# SCH_Task_10_1.net
KiCad netlist of a schematic drawn in EasyEDA
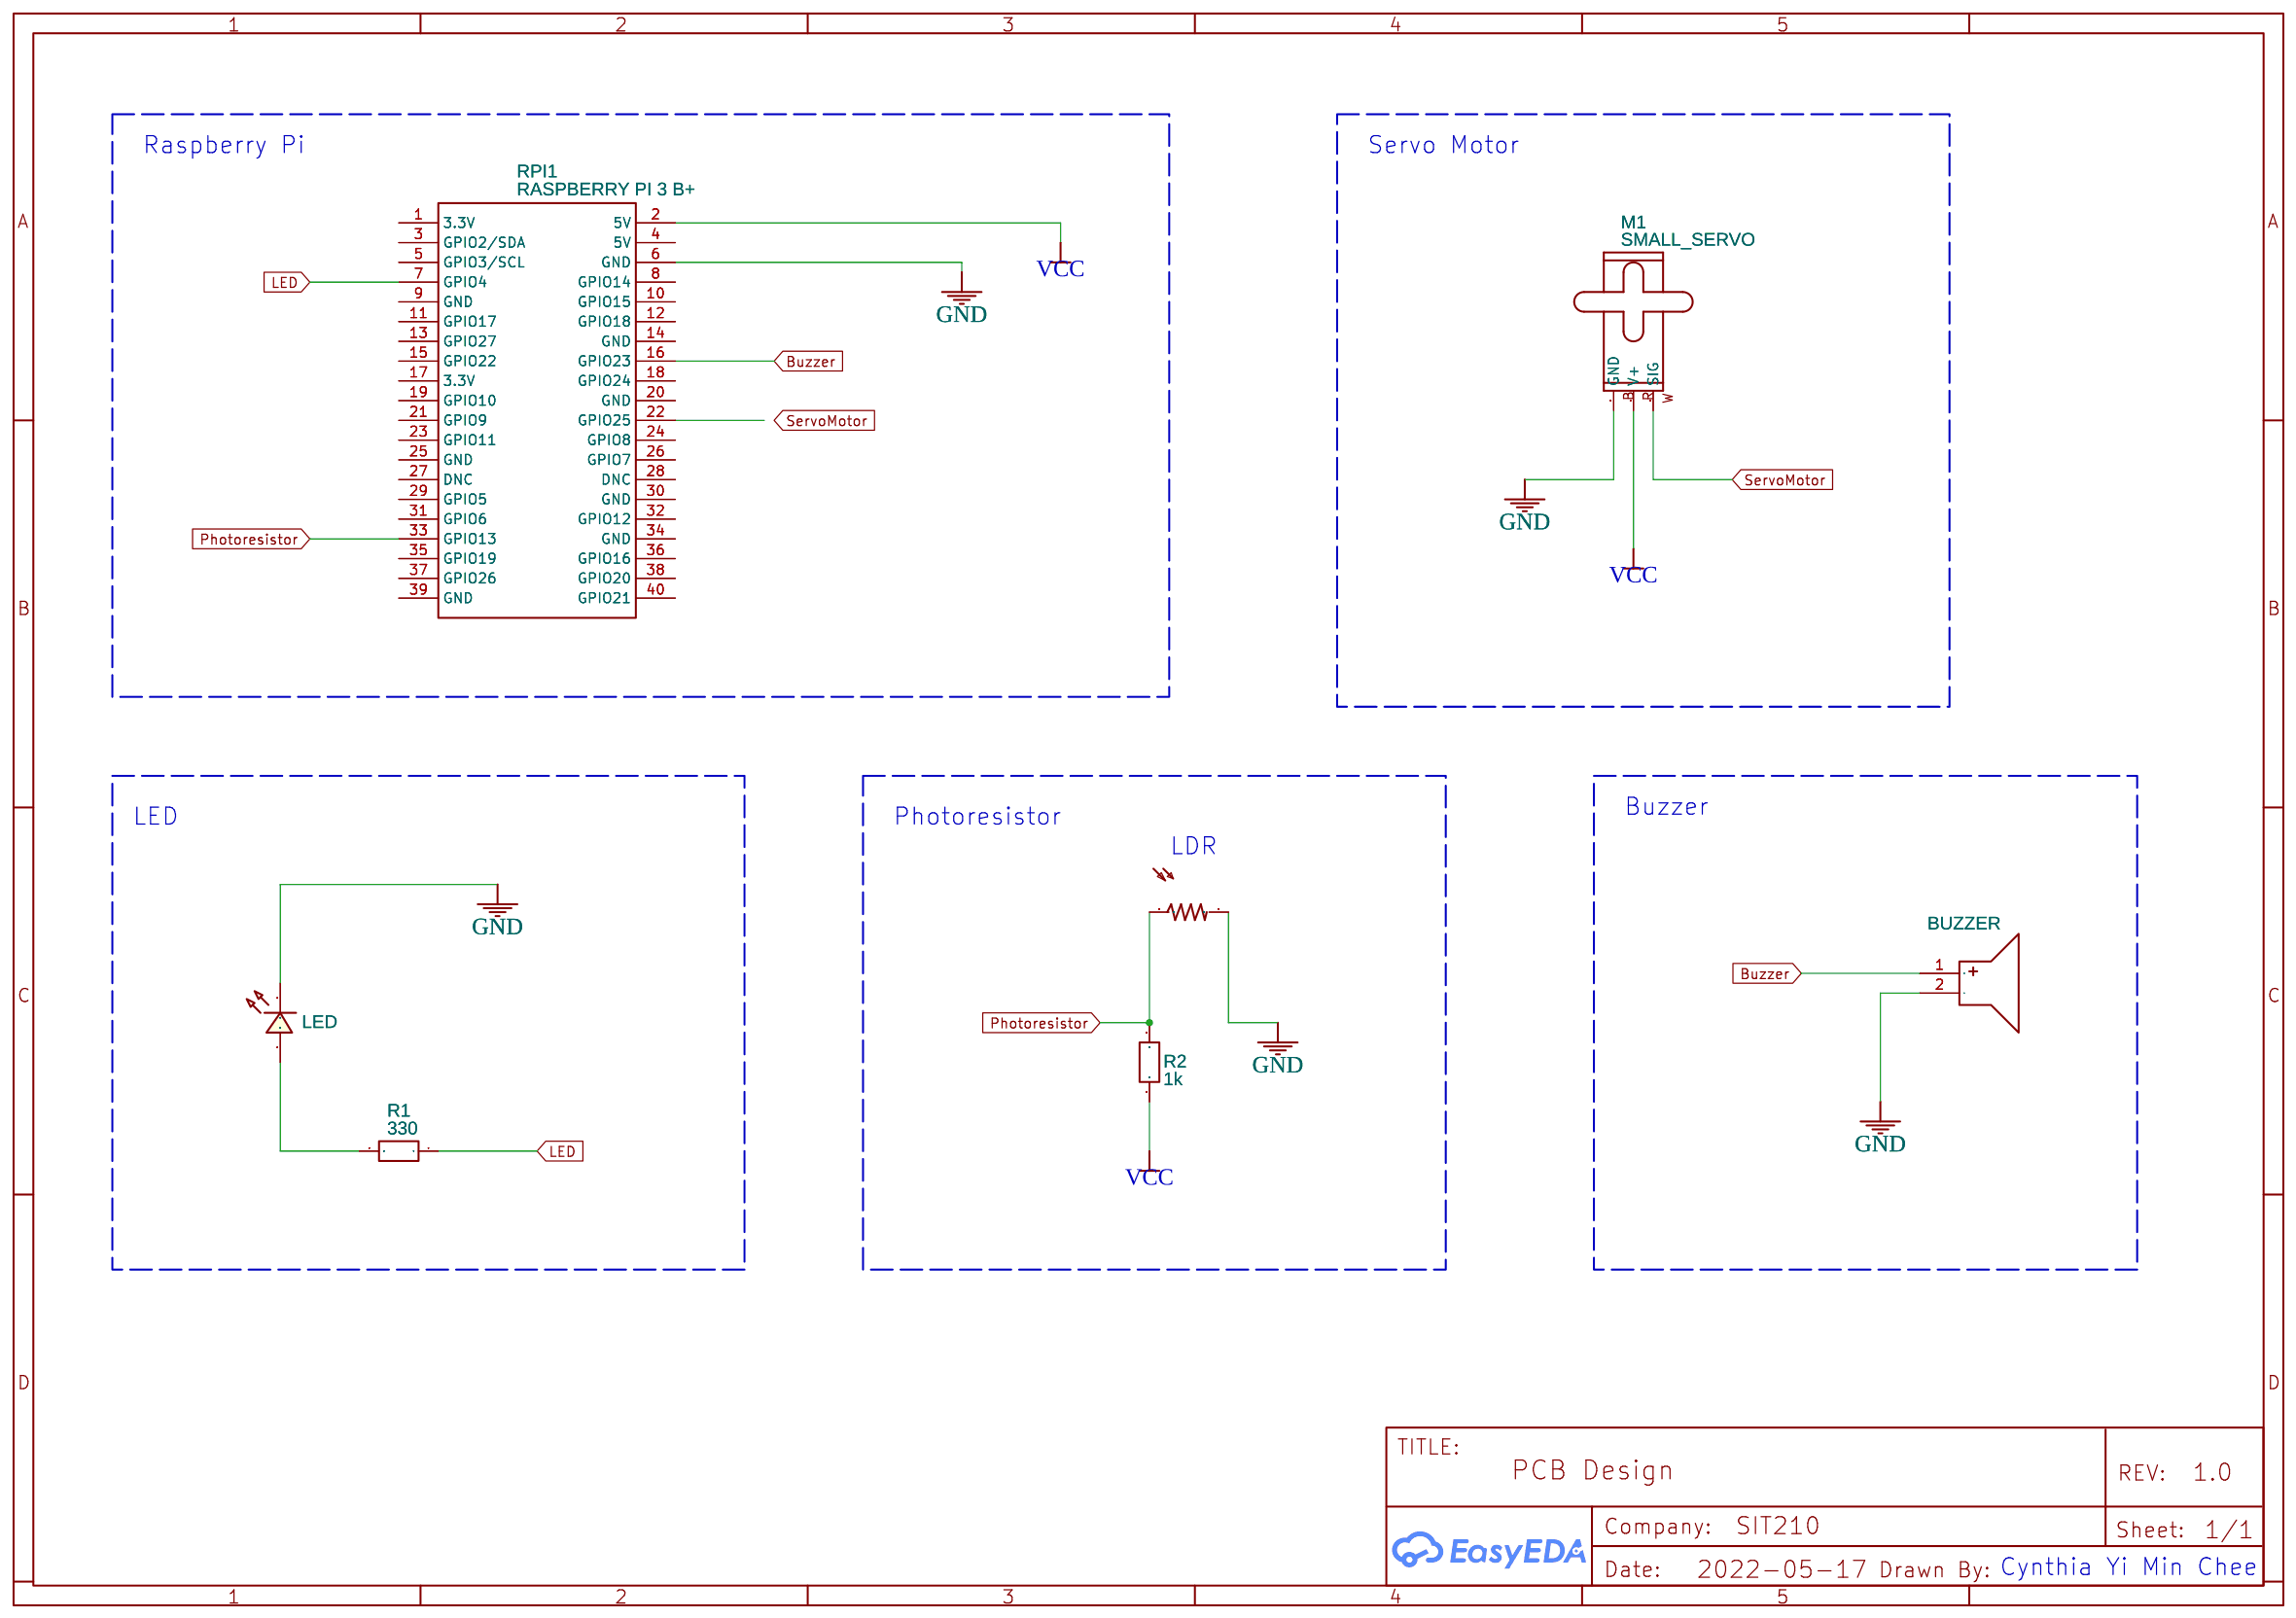
[diagram p0: schematic sheet]

(export (version "E")
  (design (tool "Eeschema 10.0.6"))
  (components
    (comp (ref "BUZZER")
      (value "BUZZER.9032")
      (fields (field (name "BOM_Supplier Part") "C9900002564"))
      (libsource (lib "") (part "BUZZER.9032"))
    )
    (comp (ref "LDR1") (value "LDR") (libsource (lib "") (part "LDR1")))
    (comp (ref "LED")
      (value "LED-0603_R")
      (fields
        (field (name "BOM_Manufacturer Part") "19-217/R6C-AL1M2VY/3T")
        (field (name "BOM_Supplier Part") "C72044")
      )
      (libsource (lib "") (part "LED-0603_R"))
    )
    (comp (ref "M1") (value "SMALL_SERVO") (libsource (lib "") (part "SMALL_SERVO")))
    (comp (ref "R1") (value "330") (libsource (lib "") (part "R_0603_EU")))
    (comp (ref "R2") (value "1k") (libsource (lib "") (part "R_0603_EU_1")))
    (comp (ref "RPI1")
      (value "RASPBERRY PI 3 B+")
      (fields
        (field (name "Manufacturer") "Raspberry Pi")
        (field (name "BOM_Manufacturer Part") "Raspberry Pi 3 - Model B+ - 1.4GHz Cortex-A53 with 1GB RAM")
        (field (name "BOM_Supplier Part") "3775")
      )
      (libsource (lib "") (part "RASPBERRY PI 3 B+"))
    )
  )
  (nets
    (net (code "1") (name "Buzzer") (class "Default")
      (node (ref "BUZZER") (pin "1") (pinfunction "+_1") (pintype "unspecified"))
      (node (ref "RPI1") (pin "16") (pinfunction "GPIO23_16") (pintype "bidirectional"))
    )
    (net (code "2") (name "GND") (class "Default")
      (node (ref "BUZZER") (pin "2") (pinfunction "-_2") (pintype "unspecified"))
      (node (ref "LDR1") (pin "2") (pinfunction "2_2") (pintype "bidirectional"))
      (node (ref "LED") (pin "2") (pinfunction "2_2") (pintype "unspecified"))
      (node (ref "M1") (pin "3") (pinfunction "GND_3") (pintype "unspecified"))
      (node (ref "RPI1") (pin "6") (pinfunction "GND_6") (pintype "unspecified"))
    )
    (net (code "3") (name "LED") (class "Default")
      (node (ref "R1") (pin "1") (pinfunction "1_1") (pintype "unspecified"))
      (node (ref "RPI1") (pin "7") (pinfunction "GPIO4_7") (pintype "bidirectional"))
    )
    (net (code "4") (name "Net-(LED-Pad1)") (class "Default")
      (node (ref "LED") (pin "1") (pinfunction "1_1") (pintype "unspecified"))
      (node (ref "R1") (pin "2") (pinfunction "2_2") (pintype "unspecified"))
    )
    (net (code "5") (name "Photoresistor") (class "Default")
      (node (ref "LDR1") (pin "1") (pinfunction "1_1") (pintype "bidirectional"))
      (node (ref "R2") (pin "2") (pinfunction "2_2") (pintype "unspecified"))
      (node (ref "RPI1") (pin "33") (pinfunction "GPIO13_33") (pintype "bidirectional"))
    )
    (net (code "6") (name "ServoMotor") (class "Default")
      (node (ref "M1") (pin "1") (pinfunction "SIG_1") (pintype "unspecified"))
    )
    (net (code "7") (name "VCC") (class "Default")
      (node (ref "M1") (pin "2") (pinfunction "V+_2") (pintype "unspecified"))
      (node (ref "R2") (pin "1") (pinfunction "1_1") (pintype "unspecified"))
      (node (ref "RPI1") (pin "2") (pinfunction "5V_2") (pintype "passive"))
    )
    (net (code "8") (name "unconnected-(RPI1-3.3V-Pad1)") (class "Default")
      (node (ref "RPI1") (pin "1") (pinfunction "3.3V_1") (pintype "passive"))
    )
    (net (code "9") (name "unconnected-(RPI1-3.3V-Pad17)") (class "Default")
      (node (ref "RPI1") (pin "17") (pinfunction "3.3V_17") (pintype "passive"))
    )
    (net (code "10") (name "unconnected-(RPI1-5V-Pad4)") (class "Default")
      (node (ref "RPI1") (pin "4") (pinfunction "5V_4") (pintype "passive"))
    )
    (net (code "11") (name "unconnected-(RPI1-DNC-Pad27)") (class "Default")
      (node (ref "RPI1") (pin "27") (pinfunction "DNC_27") (pintype "unspecified"))
    )
    (net (code "12") (name "unconnected-(RPI1-DNC-Pad28)") (class "Default")
      (node (ref "RPI1") (pin "28") (pinfunction "DNC_28") (pintype "unspecified"))
    )
    (net (code "13") (name "unconnected-(RPI1-GND-Pad9)") (class "Default")
      (node (ref "RPI1") (pin "9") (pinfunction "GND_9") (pintype "unspecified"))
    )
    (net (code "14") (name "unconnected-(RPI1-GND-Pad14)") (class "Default")
      (node (ref "RPI1") (pin "14") (pinfunction "GND_14") (pintype "unspecified"))
    )
    (net (code "15") (name "unconnected-(RPI1-GND-Pad20)") (class "Default")
      (node (ref "RPI1") (pin "20") (pinfunction "GND_20") (pintype "unspecified"))
    )
    (net (code "16") (name "unconnected-(RPI1-GND-Pad25)") (class "Default")
      (node (ref "RPI1") (pin "25") (pinfunction "GND_25") (pintype "unspecified"))
    )
    (net (code "17") (name "unconnected-(RPI1-GND-Pad30)") (class "Default")
      (node (ref "RPI1") (pin "30") (pinfunction "GND_30") (pintype "unspecified"))
    )
    (net (code "18") (name "unconnected-(RPI1-GND-Pad34)") (class "Default")
      (node (ref "RPI1") (pin "34") (pinfunction "GND_34") (pintype "unspecified"))
    )
    (net (code "19") (name "unconnected-(RPI1-GND-Pad39)") (class "Default")
      (node (ref "RPI1") (pin "39") (pinfunction "GND_39") (pintype "unspecified"))
    )
    (net (code "20") (name "unconnected-(RPI1-GPIO2{slash}SDA-Pad3)") (class "Default")
      (node (ref "RPI1") (pin "3") (pinfunction "GPIO2/SDA_3") (pintype "bidirectional"))
    )
    (net (code "21") (name "unconnected-(RPI1-GPIO3{slash}SCL-Pad5)") (class "Default")
      (node (ref "RPI1") (pin "5") (pinfunction "GPIO3/SCL_5") (pintype "bidirectional"))
    )
    (net (code "22") (name "unconnected-(RPI1-GPIO5-Pad29)") (class "Default")
      (node (ref "RPI1") (pin "29") (pinfunction "GPIO5_29") (pintype "bidirectional"))
    )
    (net (code "23") (name "unconnected-(RPI1-GPIO6-Pad31)") (class "Default")
      (node (ref "RPI1") (pin "31") (pinfunction "GPIO6_31") (pintype "bidirectional"))
    )
    (net (code "24") (name "unconnected-(RPI1-GPIO7-Pad26)") (class "Default")
      (node (ref "RPI1") (pin "26") (pinfunction "GPIO7_26") (pintype "bidirectional"))
    )
    (net (code "25") (name "unconnected-(RPI1-GPIO8-Pad24)") (class "Default")
      (node (ref "RPI1") (pin "24") (pinfunction "GPIO8_24") (pintype "bidirectional"))
    )
    (net (code "26") (name "unconnected-(RPI1-GPIO9-Pad21)") (class "Default")
      (node (ref "RPI1") (pin "21") (pinfunction "GPIO9_21") (pintype "bidirectional"))
    )
    (net (code "27") (name "unconnected-(RPI1-GPIO10-Pad19)") (class "Default")
      (node (ref "RPI1") (pin "19") (pinfunction "GPIO10_19") (pintype "bidirectional"))
    )
    (net (code "28") (name "unconnected-(RPI1-GPIO11-Pad23)") (class "Default")
      (node (ref "RPI1") (pin "23") (pinfunction "GPIO11_23") (pintype "bidirectional"))
    )
    (net (code "29") (name "unconnected-(RPI1-GPIO12-Pad32)") (class "Default")
      (node (ref "RPI1") (pin "32") (pinfunction "GPIO12_32") (pintype "bidirectional"))
    )
    (net (code "30") (name "unconnected-(RPI1-GPIO14-Pad8)") (class "Default")
      (node (ref "RPI1") (pin "8") (pinfunction "GPIO14_8") (pintype "bidirectional"))
    )
    (net (code "31") (name "unconnected-(RPI1-GPIO15-Pad10)") (class "Default")
      (node (ref "RPI1") (pin "10") (pinfunction "GPIO15_10") (pintype "bidirectional"))
    )
    (net (code "32") (name "unconnected-(RPI1-GPIO16-Pad36)") (class "Default")
      (node (ref "RPI1") (pin "36") (pinfunction "GPIO16_36") (pintype "bidirectional"))
    )
    (net (code "33") (name "unconnected-(RPI1-GPIO17-Pad11)") (class "Default")
      (node (ref "RPI1") (pin "11") (pinfunction "GPIO17_11") (pintype "bidirectional"))
    )
    (net (code "34") (name "unconnected-(RPI1-GPIO18-Pad12)") (class "Default")
      (node (ref "RPI1") (pin "12") (pinfunction "GPIO18_12") (pintype "bidirectional"))
    )
    (net (code "35") (name "unconnected-(RPI1-GPIO19-Pad35)") (class "Default")
      (node (ref "RPI1") (pin "35") (pinfunction "GPIO19_35") (pintype "bidirectional"))
    )
    (net (code "36") (name "unconnected-(RPI1-GPIO20-Pad38)") (class "Default")
      (node (ref "RPI1") (pin "38") (pinfunction "GPIO20_38") (pintype "bidirectional"))
    )
    (net (code "37") (name "unconnected-(RPI1-GPIO21-Pad40)") (class "Default")
      (node (ref "RPI1") (pin "40") (pinfunction "GPIO21_40") (pintype "bidirectional"))
    )
    (net (code "38") (name "unconnected-(RPI1-GPIO22-Pad15)") (class "Default")
      (node (ref "RPI1") (pin "15") (pinfunction "GPIO22_15") (pintype "bidirectional"))
    )
    (net (code "39") (name "unconnected-(RPI1-GPIO24-Pad18)") (class "Default")
      (node (ref "RPI1") (pin "18") (pinfunction "GPIO24_18") (pintype "bidirectional"))
    )
    (net (code "40") (name "unconnected-(RPI1-GPIO25-Pad22)") (class "Default")
      (node (ref "RPI1") (pin "22") (pinfunction "GPIO25_22") (pintype "bidirectional"))
    )
    (net (code "41") (name "unconnected-(RPI1-GPIO26-Pad37)") (class "Default")
      (node (ref "RPI1") (pin "37") (pinfunction "GPIO26_37") (pintype "bidirectional"))
    )
    (net (code "42") (name "unconnected-(RPI1-GPIO27-Pad13)") (class "Default")
      (node (ref "RPI1") (pin "13") (pinfunction "GPIO27_13") (pintype "bidirectional"))
    )
  )
)
